# 08-Power.net
KiCad netlist of a schematic drawn in Altium Designer
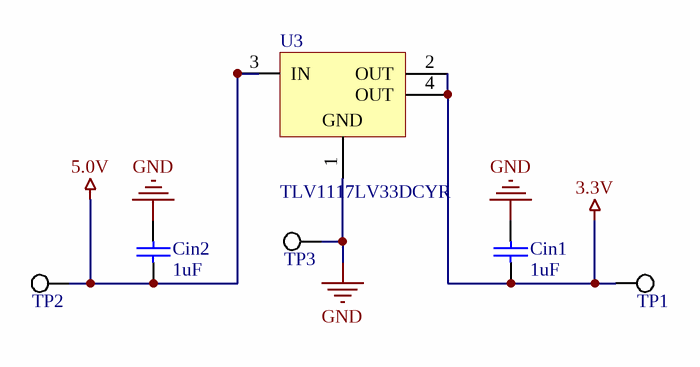
[diagram p0: 08-Power.SchDoc]

(export (version "E")
  (design (tool "Eeschema 10.0.6"))
  (components
    (comp (ref "Cin1")
      (value "C1206C105K3RACTU")
      (footprint "CAPC3216X180X50ML20T25")
      (description "Chip Capacitor, 1 uF, +/- 10%, 25 V, -55 to 125 degC, 1206 (3216 Metric), RoHS, Tape and Reel")
      (fields
        (field (name "CAPACITANCE") "1uF")
        (field (name "MANUFACTURER") "Kemet")
        (field (name "TOLERANCE") "10%")
      )
      (libsource (lib "Altium Content Vault") (part "CAP-NP-2"))
    )
    (comp (ref "Cin2")
      (value "C1206C105K3RACTU")
      (footprint "CAPC3216X180X50ML20T25")
      (description "Chip Capacitor, 1 uF, +/- 10%, 25 V, -55 to 125 degC, 1206 (3216 Metric), RoHS, Tape and Reel")
      (fields
        (field (name "CAPACITANCE") "1uF")
        (field (name "MANUFACTURER") "Kemet")
        (field (name "TOLERANCE") "10%")
      )
      (libsource (lib "Altium Content Vault") (part "CAP-NP-2"))
    )
    (comp (ref "TP1")
      (value "5019")
      (footprint "KSTN-5019_V")
      (description "Test Point, 1 Position SMD, RoHS, Tape and Reel")
      (libsource (lib "Altium Content Vault") (part "TESTPOINT_WHITE"))
    )
    (comp (ref "TP2")
      (value "5019")
      (footprint "KSTN-5019_V")
      (description "Test Point, 1 Position SMD, RoHS, Tape and Reel")
      (libsource (lib "Altium Content Vault") (part "TESTPOINT_WHITE"))
    )
    (comp (ref "TP3")
      (value "5019")
      (footprint "KSTN-5019_V")
      (description "Test Point, 1 Position SMD, RoHS, Tape and Reel")
      (libsource (lib "Altium Content Vault") (part "TESTPOINT_WHITE"))
    )
    (comp (ref "U3")
      (value "TLV1117LV33DCYR")
      (footprint "DCY0004A_N")
      (fields (field (name "MANUFACTURER") "Texas Instruments"))
      (libsource (lib "Altium Content Vault") (part "TI-TLV1117LV33DCY4"))
    )
  )
  (nets
    (net (code "1") (name "3.3V") (class "Default")
      (node (ref "Cin1") (pin "1") (pinfunction "1_1") (pintype "passive"))
      (node (ref "TP1") (pin "1") (pinfunction "1_1") (pintype "passive"))
      (node (ref "U3") (pin "2") (pinfunction "OUT_2") (pintype "power_in"))
      (node (ref "U3") (pin "4") (pinfunction "OUT_4") (pintype "power_in"))
    )
    (net (code "2") (name "5.0V") (class "Default")
      (node (ref "Cin2") (pin "1") (pinfunction "1_1") (pintype "passive"))
      (node (ref "TP2") (pin "1") (pinfunction "1_1") (pintype "passive"))
      (node (ref "U3") (pin "3") (pinfunction "IN_3") (pintype "power_in"))
    )
    (net (code "3") (name "GND") (class "Default")
      (node (ref "Cin1") (pin "2") (pinfunction "2_2") (pintype "passive"))
      (node (ref "Cin2") (pin "2") (pinfunction "2_2") (pintype "passive"))
      (node (ref "TP3") (pin "1") (pinfunction "1_1") (pintype "passive"))
      (node (ref "U3") (pin "1") (pinfunction "GND_1") (pintype "power_in"))
    )
  )
)
